# FlightController.net
KiCad netlist of a schematic drawn in Altium Designer
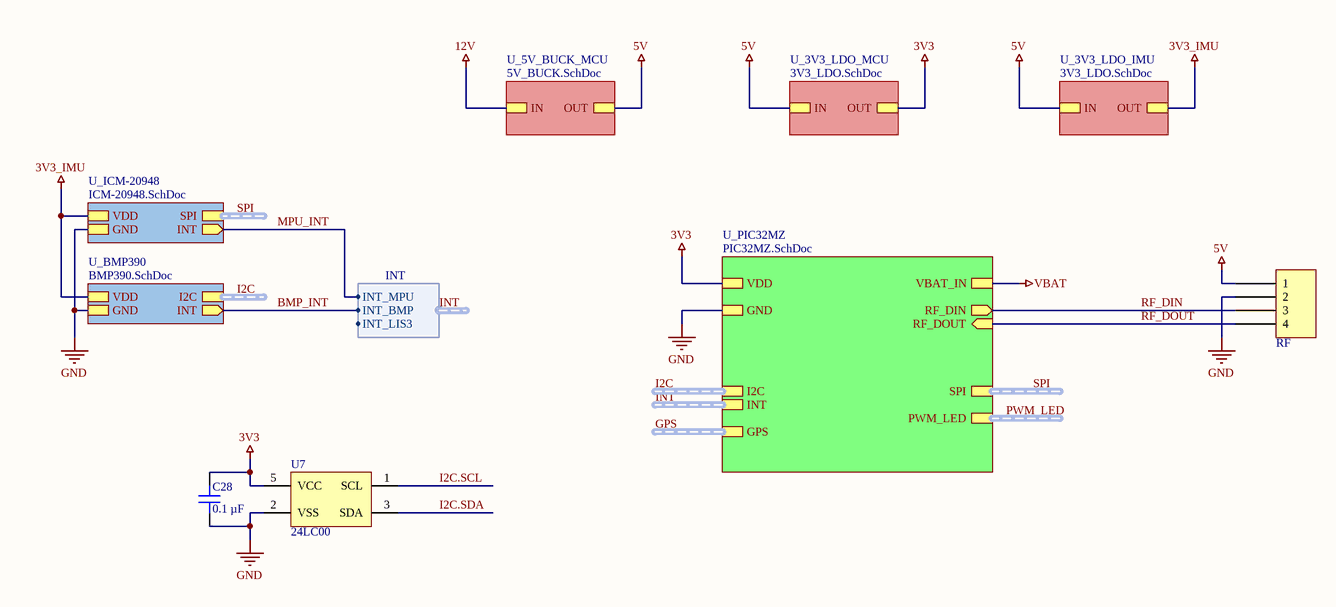
[diagram p0: FlightController.SchDoc]

(export (version "E")
  (design (tool "Eeschema 10.0.6"))
  (components
    (comp (ref "C28")
      (value "0.1 µF")
      (footprint "CAP 0402_1005")
      (description "CAP CER 0.1UF 16V X7R 0402")
      (fields (field (name "PART NUMBER") "C0402C104K4RACAUTO") (field (name "MANUFACTURER") "KEMET"))
      (libsource (lib "Celestial Altium Library - altium_library") (part "Capacitor"))
    )
    (comp (ref "RF")
      (value "SM04B-SRSS-TB(LF)(SN)")
      (footprint "JST SM04B-SRSS-TB")
      (description "CONN HEADER SMD R/A 4POS 1MM")
      (fields (field (name "MANUFACTURER") "JST Sales America Inc."))
      (libsource (lib "Celestial Altium Library - altium_library") (part "4 Pin"))
    )
    (comp (ref "U7")
      (value "24LC00")
      (footprint "SOT-23-5")
      (description "EEPROM")
      (libsource (lib "IC") (part "24LC00"))
    )
  )
  (nets
    (net (code "8") (name "/I2C.SCL") (class "Default")
      (node (ref "U7") (pin "1") (pinfunction "SCL_1") (pintype "passive"))
    )
    (net (code "9") (name "/I2C.SDA") (class "Default")
      (node (ref "U7") (pin "3") (pinfunction "SDA_3") (pintype "passive"))
    )
    (net (code "12") (name "/RF_DIN") (class "Default")
      (node (ref "RF") (pin "3") (pinfunction "3_3") (pintype "passive"))
    )
    (net (code "13") (name "/RF_DOUT") (class "Default")
      (node (ref "RF") (pin "4") (pinfunction "4_4") (pintype "passive"))
    )
    (net (code "19") (name "3V3") (class "Default")
      (node (ref "C28") (pin "2") (pinfunction "2_2") (pintype "passive"))
      (node (ref "U7") (pin "5") (pinfunction "VCC_5") (pintype "passive"))
    )
    (net (code "21") (name "5V") (class "Default")
      (node (ref "RF") (pin "1") (pinfunction "1_1") (pintype "passive"))
    )
    (net (code "23") (name "GND") (class "Default")
      (node (ref "C28") (pin "1") (pinfunction "1_1") (pintype "passive"))
      (node (ref "RF") (pin "2") (pinfunction "2_2") (pintype "passive"))
      (node (ref "U7") (pin "2") (pinfunction "VSS_2") (pintype "passive"))
    )
  )
)
